# Thrusters.net
KiCad netlist of a schematic drawn in Altium Designer
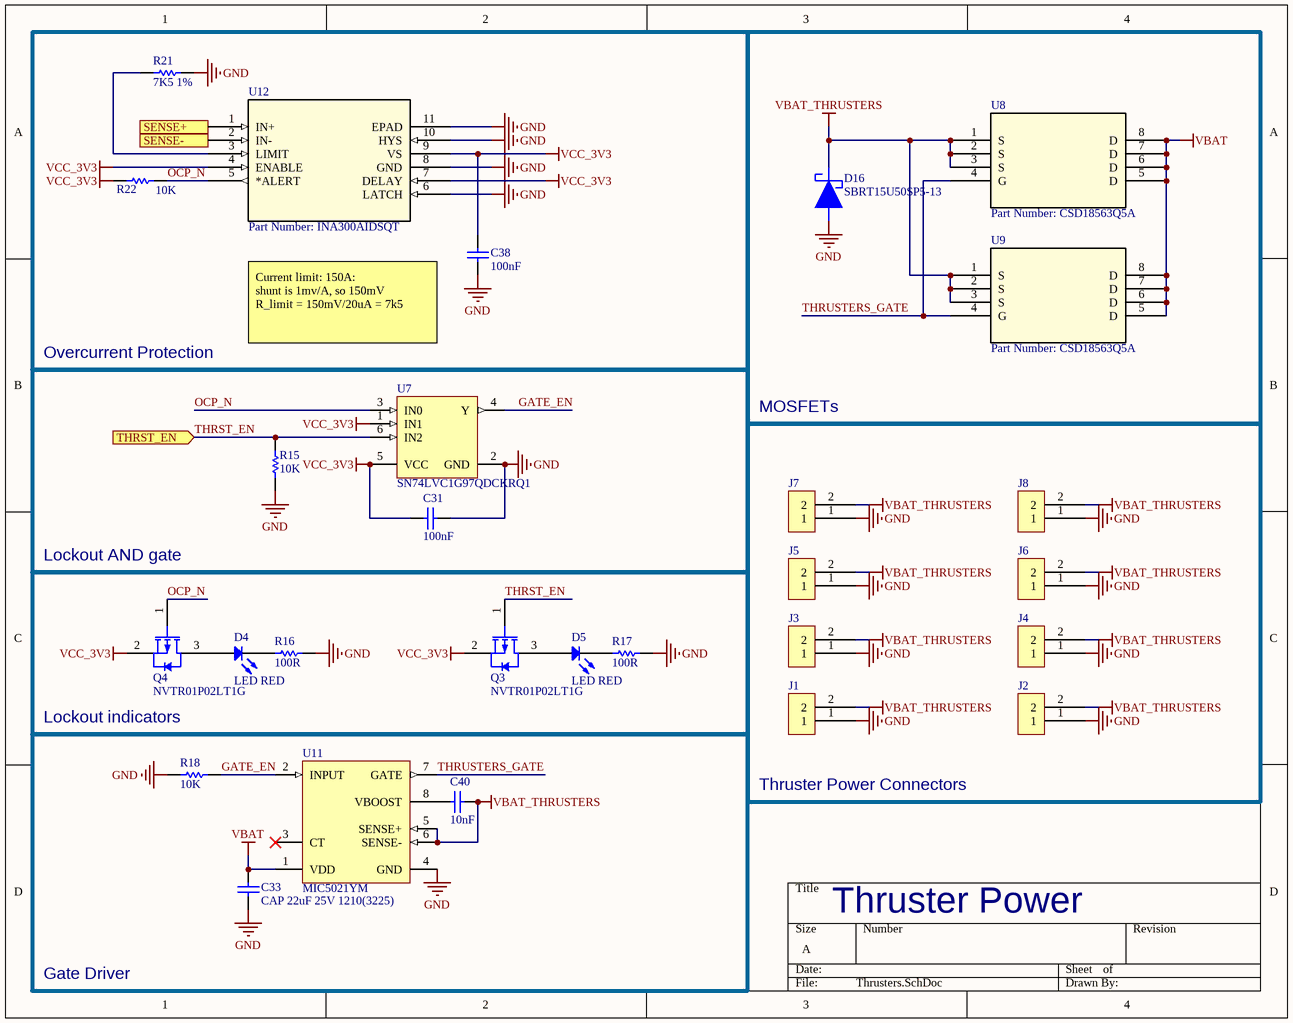
[diagram p0: Thrusters.SchDoc]

(export (version "E")
  (design (tool "Eeschema 10.0.6"))
  (components
    (comp (ref "C31")
      (value "100nF")
      (footprint "CAPC0603(1608)100_N")
      (description "CAP 100nF 10V ±10% 0603 (1608 Metric) Thickness 1mm SMD")
      (fields (field (name "TOLERANCE") "Â±10%"))
      (libsource (lib "Altium Content Vault") (part "CAP"))
    )
    (comp (ref "C33")
      (value "CAP 22uF 25V 1210(3225)")
      (footprint "CAPC1210(3225)220_L")
      (description "CAP 22uF 25V -20% to +80% 1210 (3225 Metric) Thickness 2.2mm SMD")
      (fields (field (name "TOLERANCE") "-20% to +80%"))
      (libsource (lib "Altium Content Vault") (part "CAP"))
    )
    (comp (ref "C38")
      (value "100nF")
      (footprint "CAPC0603(1608)100_N")
      (description "CAP 100nF 10V ±10% 0603 (1608 Metric) Thickness 1mm SMD")
      (fields (field (name "TOLERANCE") "Â±10%"))
      (libsource (lib "Altium Content Vault") (part "CAP"))
    )
    (comp (ref "C40")
      (value "10nF")
      (footprint "CAPC0603(1608)100_L")
      (description "CAP 10nF 25V ±2% 0603 (1608 Metric) Thickness 1mm SMD")
      (fields (field (name "TOLERANCE") "Â±2%"))
      (libsource (lib "Altium Content Vault") (part "CAP"))
    )
    (comp (ref "D4")
      (value "LED RED")
      (footprint "LED_0805")
      (description "led\r\n LTST-C171KRKT")
      (fields
        (field (name "MANUFACTURER") "Lite-On Inc.")
        (field (name "MANUFACTURER PART NUMBER") "LTST-C171KRKT")
      )
      (libsource (lib "CMR_Miscellaneous_Devices") (part "LED0"))
    )
    (comp (ref "D5")
      (value "LED RED")
      (footprint "LED_0805")
      (description "led\r\n LTST-C171KRKT")
      (fields
        (field (name "MANUFACTURER") "Lite-On Inc.")
        (field (name "MANUFACTURER PART NUMBER") "LTST-C171KRKT")
      )
      (libsource (lib "CMR_Miscellaneous_Devices") (part "LED0"))
    )
    (comp (ref "D16")
      (value "SBRT15U50SP5-13")
      (footprint "SBRT15U50SP5-13")
      (fields (field (name "MANUFACTURER") "Diodes Incorporated"))
      (libsource (lib "CMR_Miscellaneous_Devices") (part "SBRT15U50SP5-13"))
    )
    (comp (ref "J1")
      (value "~")
      (footprint "2-pin Megafit RA")
      (libsource (lib "TAUV-Lib") (part "2-pin megafit"))
    )
    (comp (ref "J2")
      (value "~")
      (footprint "2-pin Megafit RA")
      (libsource (lib "TAUV-Lib") (part "2-pin megafit"))
    )
    (comp (ref "J3")
      (value "~")
      (footprint "2-pin Megafit RA")
      (libsource (lib "TAUV-Lib") (part "2-pin megafit"))
    )
    (comp (ref "J4")
      (value "~")
      (footprint "2-pin Megafit RA")
      (libsource (lib "TAUV-Lib") (part "2-pin megafit"))
    )
    (comp (ref "J5")
      (value "~")
      (footprint "2-pin Megafit RA")
      (libsource (lib "TAUV-Lib") (part "2-pin megafit"))
    )
    (comp (ref "J6")
      (value "~")
      (footprint "2-pin Megafit RA")
      (libsource (lib "TAUV-Lib") (part "2-pin megafit"))
    )
    (comp (ref "J7")
      (value "~")
      (footprint "2-pin Megafit RA")
      (libsource (lib "TAUV-Lib") (part "2-pin megafit"))
    )
    (comp (ref "J8")
      (value "~")
      (footprint "2-pin Megafit RA")
      (libsource (lib "TAUV-Lib") (part "2-pin megafit"))
    )
    (comp (ref "Q3")
      (value "NVTR01P02LT1G")
      (footprint "ONSC-SOT-23-3-318-08_V")
      (description "Power MOSFET, -20 V, -1.3 A, P-Channel, 3-Pin SOT-23, Pb-Free, Tape and Reel")
      (fields (field (name "MANUFACTURER") "On Semiconductor"))
      (libsource (lib "Altium Content Vault") (part "ONSC-PMOS-G1S2D3-3_D"))
    )
    (comp (ref "Q4")
      (value "NVTR01P02LT1G")
      (footprint "ONSC-SOT-23-3-318-08_V")
      (description "Power MOSFET, -20 V, -1.3 A, P-Channel, 3-Pin SOT-23, Pb-Free, Tape and Reel")
      (fields (field (name "MANUFACTURER") "On Semiconductor"))
      (libsource (lib "Altium Content Vault") (part "ONSC-PMOS-G1S2D3-3_D"))
    )
    (comp (ref "R15")
      (value "10K")
      (footprint "RESC0603(1608)_N")
      (description "10K 0.1W 5% 0603 (1608 Metric)  SMD")
      (fields (field (name "TOLERANCE") "5 %") (field (name "POWER") "0.1 W"))
      (libsource (lib "Altium Content Vault") (part "RES"))
    )
    (comp (ref "R16")
      (value "100R")
      (footprint "RESC0603(1608)_N")
      (description "100R 0.1W 5% 0603 (1608 Metric)  SMD")
      (fields (field (name "TOLERANCE") "5 %") (field (name "POWER") "0.1 W"))
      (libsource (lib "Altium Content Vault") (part "RES"))
    )
    (comp (ref "R17")
      (value "100R")
      (footprint "RESC0603(1608)_N")
      (description "100R 0.1W 5% 0603 (1608 Metric)  SMD")
      (fields (field (name "TOLERANCE") "5 %") (field (name "POWER") "0.1 W"))
      (libsource (lib "Altium Content Vault") (part "RES"))
    )
    (comp (ref "R18")
      (value "10K")
      (footprint "RESC0603(1608)_N")
      (description "10K 0.1W 5% 0603 (1608 Metric)  SMD")
      (fields (field (name "TOLERANCE") "5 %") (field (name "POWER") "0.1 W"))
      (libsource (lib "Altium Content Vault") (part "RES"))
    )
    (comp (ref "R21")
      (value "7K5 1%")
      (footprint "RESC0603(1608)_N")
      (description "7K5 0.1W 1% 0603 (1608 Metric)  SMD")
      (fields (field (name "TOLERANCE") "1 %") (field (name "POWER") "0.1 W"))
      (libsource (lib "Altium Content Vault") (part "RES"))
    )
    (comp (ref "R22")
      (value "10K")
      (footprint "RESC0603(1608)_N")
      (description "10K 0.1W 5% 0603 (1608 Metric)  SMD")
      (fields (field (name "TOLERANCE") "5 %") (field (name "POWER") "0.1 W"))
      (libsource (lib "Altium Content Vault") (part "RES"))
    )
    (comp (ref "U7")
      (value "SN74LVC1G97QDCKRQ1")
      (footprint "DCK0006A_L")
      (description "Automotive Catalog Configurable Multiple-Function Gate, DCK0006A, LARGE T&R")
      (fields
        (field (name "MANUFACTURER") "Texas Instruments")
        (field (name "GENERIC PART NUMBER") "SN74LVC1G97-Q1")
      )
      (libsource (lib "Altium Content Vault") (part "TI-SN74XXX1GXX-6"))
    )
    (comp (ref "U8")
      (value "Part Number: CSD18563Q5A")
      (footprint "DQJ8")
      (description "No Description Available")
      (fields
        (field (name "MANUFACTURER_PART_NUMBER") "CSD18563Q5A")
        (field (name "COPYRIGHT") "Copyright (C) 2018 Accelerated Designs. All rights reserved")
      )
      (libsource (lib "Tauv-Lib") (part "CSD18563Q5A"))
    )
    (comp (ref "U9")
      (value "Part Number: CSD18563Q5A")
      (footprint "DQJ8")
      (description "No Description Available")
      (fields
        (field (name "MANUFACTURER_PART_NUMBER") "CSD18563Q5A")
        (field (name "COPYRIGHT") "Copyright (C) 2018 Accelerated Designs. All rights reserved")
      )
      (libsource (lib "Tauv-Lib") (part "CSD18563Q5A"))
    )
    (comp (ref "U11")
      (value "MIC5021YM")
      (footprint "MICL-SOICN-8LD-PL-1_V")
      (description "High-Speed High-Side MOSFET Driver, 12 to 36 V, -40 to 85 degC, 8-Pin SOIC, RoHS, Tube")
      (libsource (lib "Altium Content Vault") (part "MICL-MIC5021B_YM-8"))
    )
    (comp (ref "U12")
      (value "Part Number: INA300AIDSQT")
      (footprint "DSQ10_P9X1P5")
      (description "No Description Available")
      (fields
        (field (name "MANUFACTURER_PART_NUMBER") "INA300AIDSQT")
        (field (name "COPYRIGHT") "Copyright (C) 2018 Accelerated Designs. All rights reserved")
      )
      (libsource (lib "Tauv-Lib") (part "INA300AIDSQT"))
    )
  )
  (nets
    (net (code "1") (name "/GATE_EN") (class "Default")
      (node (ref "R18") (pin "1") (pinfunction "1_1") (pintype "passive"))
      (node (ref "U11") (pin "2") (pinfunction "INPUT_2") (pintype "input"))
      (node (ref "U7") (pin "4") (pinfunction "Y_4") (pintype "output"))
    )
    (net (code "2") (name "/OCP_N") (class "Default")
      (node (ref "Q4") (pin "1") (pinfunction "G_1") (pintype "passive"))
      (node (ref "R22") (pin "1") (pinfunction "1_1") (pintype "passive"))
      (node (ref "U12") (pin "5") (pinfunction "*ALERT_5") (pintype "output"))
      (node (ref "U7") (pin "3") (pinfunction "IN0_3") (pintype "input"))
    )
    (net (code "3") (name "/SENSE+") (class "Default")
      (node (ref "U12") (pin "1") (pinfunction "IN+_1") (pintype "input"))
    )
    (net (code "4") (name "/SENSE-") (class "Default")
      (node (ref "U12") (pin "2") (pinfunction "IN-_2") (pintype "input"))
    )
    (net (code "5") (name "/THRST_EN") (class "Default")
      (node (ref "Q3") (pin "1") (pinfunction "G_1") (pintype "passive"))
      (node (ref "R15") (pin "1") (pinfunction "1_1") (pintype "passive"))
      (node (ref "U7") (pin "6") (pinfunction "IN2_6") (pintype "input"))
    )
    (net (code "6") (name "/THRUSTERS_GATE") (class "Default")
      (node (ref "U11") (pin "7") (pinfunction "GATE_7") (pintype "output"))
      (node (ref "U8") (pin "4") (pinfunction "G_4") (pintype "passive"))
      (node (ref "U9") (pin "4") (pinfunction "G_4") (pintype "passive"))
    )
    (net (code "7") (name "GND") (class "Default")
      (node (ref "C31") (pin "1") (pinfunction "1_1") (pintype "passive"))
      (node (ref "C33") (pin "1") (pinfunction "1_1") (pintype "passive"))
      (node (ref "C38") (pin "1") (pinfunction "1_1") (pintype "passive"))
      (node (ref "D16") (pin "1") (pinfunction "1_1") (pintype "passive"))
      (node (ref "J1") (pin "1") (pinfunction "1_1") (pintype "passive"))
      (node (ref "J2") (pin "1") (pinfunction "1_1") (pintype "passive"))
      (node (ref "J3") (pin "1") (pinfunction "1_1") (pintype "passive"))
      (node (ref "J4") (pin "1") (pinfunction "1_1") (pintype "passive"))
      (node (ref "J5") (pin "1") (pinfunction "1_1") (pintype "passive"))
      (node (ref "J6") (pin "1") (pinfunction "1_1") (pintype "passive"))
      (node (ref "J7") (pin "1") (pinfunction "1_1") (pintype "passive"))
      (node (ref "J8") (pin "1") (pinfunction "1_1") (pintype "passive"))
      (node (ref "R15") (pin "2") (pinfunction "2_2") (pintype "passive"))
      (node (ref "R16") (pin "2") (pinfunction "2_2") (pintype "passive"))
      (node (ref "R17") (pin "2") (pinfunction "2_2") (pintype "passive"))
      (node (ref "R18") (pin "2") (pinfunction "2_2") (pintype "passive"))
      (node (ref "R21") (pin "2") (pinfunction "2_2") (pintype "passive"))
      (node (ref "U11") (pin "4") (pinfunction "GND_4") (pintype "power_in"))
      (node (ref "U12") (pin "10") (pinfunction "HYS_10") (pintype "input"))
      (node (ref "U12") (pin "11") (pinfunction "EPAD_11") (pintype "passive"))
      (node (ref "U12") (pin "6") (pinfunction "LATCH_6") (pintype "input"))
      (node (ref "U12") (pin "8") (pinfunction "GND_8") (pintype "power_in"))
      (node (ref "U7") (pin "2") (pinfunction "GND_2") (pintype "power_in"))
    )
    (net (code "8") (name "Net-(D4-A)") (class "Default")
      (node (ref "D4") (pin "2") (pinfunction "A_2") (pintype "passive"))
      (node (ref "Q4") (pin "3") (pinfunction "D_3") (pintype "passive"))
    )
    (net (code "9") (name "Net-(D4-K)") (class "Default")
      (node (ref "D4") (pin "1") (pinfunction "K_1") (pintype "passive"))
      (node (ref "R16") (pin "1") (pinfunction "1_1") (pintype "passive"))
    )
    (net (code "10") (name "Net-(D5-A)") (class "Default")
      (node (ref "D5") (pin "2") (pinfunction "A_2") (pintype "passive"))
      (node (ref "Q3") (pin "3") (pinfunction "D_3") (pintype "passive"))
    )
    (net (code "11") (name "Net-(D5-K)") (class "Default")
      (node (ref "D5") (pin "1") (pinfunction "K_1") (pintype "passive"))
      (node (ref "R17") (pin "1") (pinfunction "1_1") (pintype "passive"))
    )
    (net (code "12") (name "Net-(U11-VBOOST)") (class "Default")
      (node (ref "C40") (pin "1") (pinfunction "1_1") (pintype "passive"))
      (node (ref "U11") (pin "8") (pinfunction "VBOOST_8") (pintype "power_in"))
    )
    (net (code "13") (name "Net-(U12-LIMIT)") (class "Default")
      (node (ref "R21") (pin "1") (pinfunction "1_1") (pintype "passive"))
      (node (ref "U12") (pin "3") (pinfunction "LIMIT_3") (pintype "input"))
    )
    (net (code "14") (name "VBAT") (class "Default")
      (node (ref "C33") (pin "2") (pinfunction "2_2") (pintype "passive"))
      (node (ref "U11") (pin "1") (pinfunction "VDD_1") (pintype "power_in"))
      (node (ref "U8") (pin "5") (pinfunction "D_5") (pintype "passive"))
      (node (ref "U8") (pin "6") (pinfunction "D_6") (pintype "passive"))
      (node (ref "U8") (pin "7") (pinfunction "D_7") (pintype "passive"))
      (node (ref "U8") (pin "8") (pinfunction "D_8") (pintype "passive"))
      (node (ref "U9") (pin "5") (pinfunction "D_5") (pintype "passive"))
      (node (ref "U9") (pin "6") (pinfunction "D_6") (pintype "passive"))
      (node (ref "U9") (pin "7") (pinfunction "D_7") (pintype "passive"))
      (node (ref "U9") (pin "8") (pinfunction "D_8") (pintype "passive"))
    )
    (net (code "15") (name "VBAT_THRUSTERS") (class "Default")
      (node (ref "C40") (pin "2") (pinfunction "2_2") (pintype "passive"))
      (node (ref "D16") (pin "2") (pinfunction "2_2") (pintype "passive"))
      (node (ref "J1") (pin "2") (pinfunction "2_2") (pintype "passive"))
      (node (ref "J2") (pin "2") (pinfunction "2_2") (pintype "passive"))
      (node (ref "J3") (pin "2") (pinfunction "2_2") (pintype "passive"))
      (node (ref "J4") (pin "2") (pinfunction "2_2") (pintype "passive"))
      (node (ref "J5") (pin "2") (pinfunction "2_2") (pintype "passive"))
      (node (ref "J6") (pin "2") (pinfunction "2_2") (pintype "passive"))
      (node (ref "J7") (pin "2") (pinfunction "2_2") (pintype "passive"))
      (node (ref "J8") (pin "2") (pinfunction "2_2") (pintype "passive"))
      (node (ref "U11") (pin "5") (pinfunction "SENSE+_5") (pintype "input"))
      (node (ref "U11") (pin "6") (pinfunction "SENSE-_6") (pintype "input"))
      (node (ref "U8") (pin "1") (pinfunction "S_1") (pintype "passive"))
      (node (ref "U8") (pin "2") (pinfunction "S_2") (pintype "passive"))
      (node (ref "U8") (pin "3") (pinfunction "S_3") (pintype "passive"))
      (node (ref "U9") (pin "1") (pinfunction "S_1") (pintype "passive"))
      (node (ref "U9") (pin "2") (pinfunction "S_2") (pintype "passive"))
      (node (ref "U9") (pin "3") (pinfunction "S_3") (pintype "passive"))
    )
    (net (code "16") (name "VCC_3V3") (class "Default")
      (node (ref "C31") (pin "2") (pinfunction "2_2") (pintype "passive"))
      (node (ref "C38") (pin "2") (pinfunction "2_2") (pintype "passive"))
      (node (ref "Q3") (pin "2") (pinfunction "S_2") (pintype "passive"))
      (node (ref "Q4") (pin "2") (pinfunction "S_2") (pintype "passive"))
      (node (ref "R22") (pin "2") (pinfunction "2_2") (pintype "passive"))
      (node (ref "U12") (pin "4") (pinfunction "ENABLE_4") (pintype "input"))
      (node (ref "U12") (pin "7") (pinfunction "DELAY_7") (pintype "input"))
      (node (ref "U12") (pin "9") (pinfunction "VS_9") (pintype "power_in"))
      (node (ref "U7") (pin "1") (pinfunction "IN1_1") (pintype "input"))
      (node (ref "U7") (pin "5") (pinfunction "VCC_5") (pintype "power_in"))
    )
    (net (code "17") (name "unconnected-(U11-CT-Pad3)") (class "Default")
      (node (ref "U11") (pin "3") (pinfunction "CT_3") (pintype "passive+no_connect"))
    )
  )
)
